# AVRI2CIO_V0_3_LEVEL0.net
KiCad netlist of a schematic drawn in EAGLE
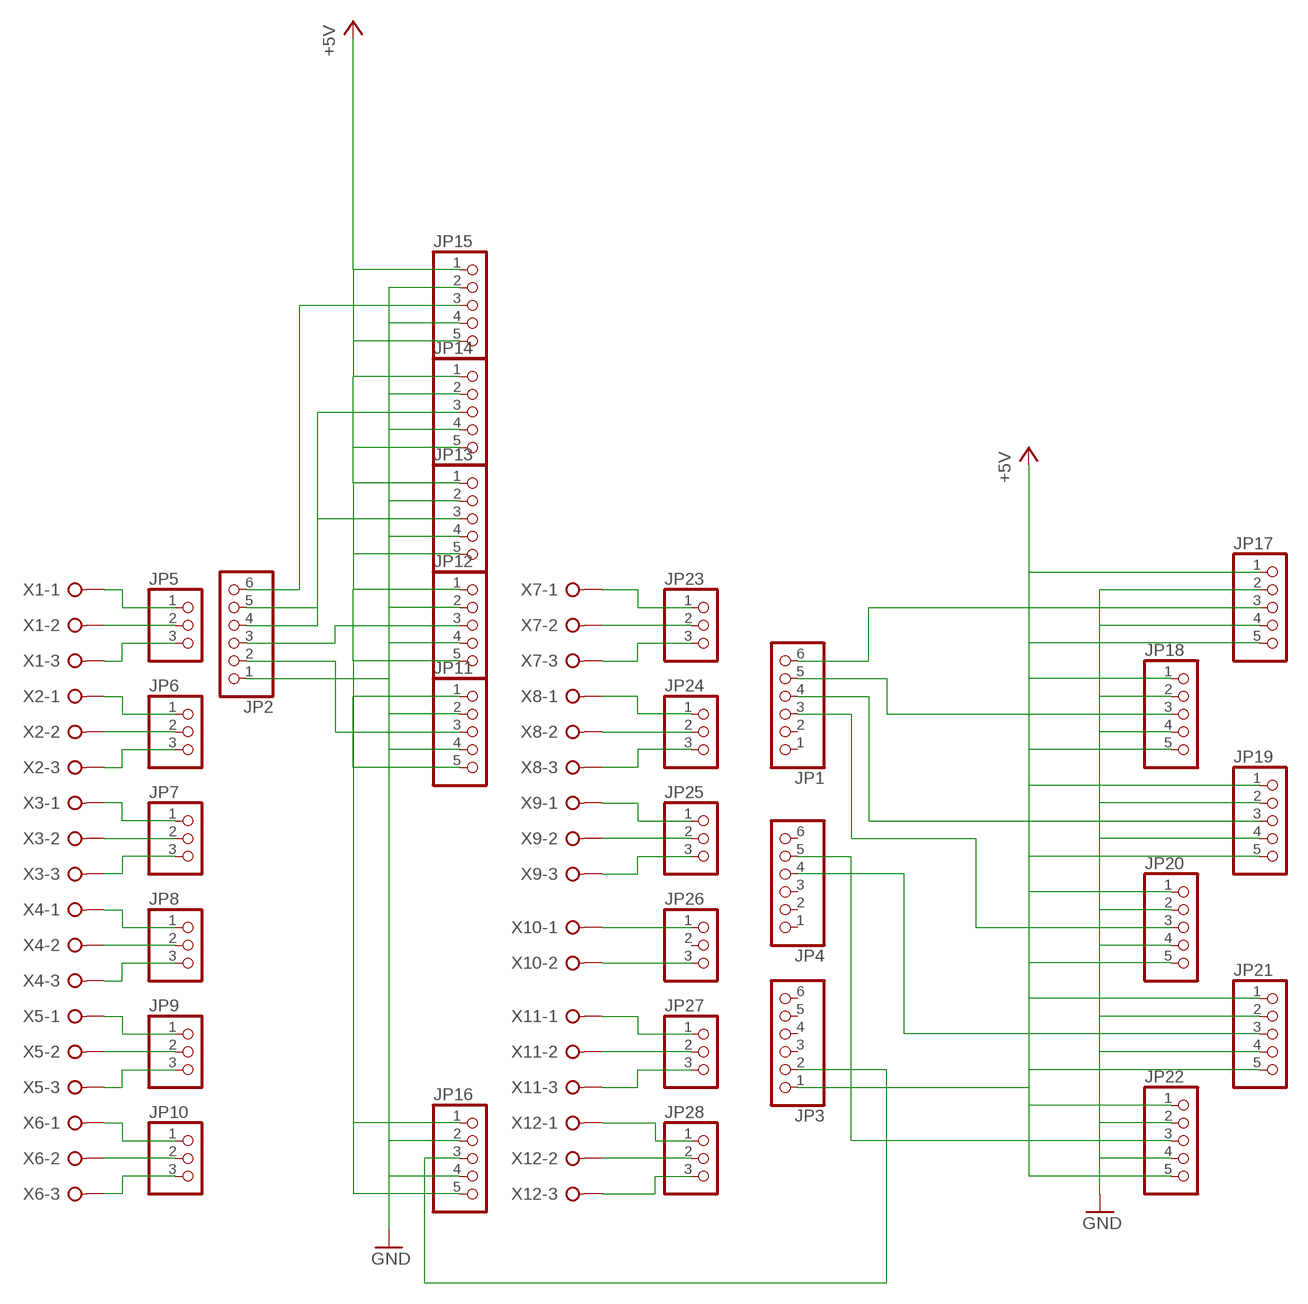
[diagram p0: schematic, sheet 1]

(export (version "E")
  (design (tool "Eeschema 10.0.6"))
  (components
    (comp (ref "JP1")
      (value "PINHD-1X6")
      (footprint "eagle-import:1X06")
      (libsource (lib "eagle-import") (part "PINHD-1X6"))
    )
    (comp (ref "JP2")
      (value "PINHD-1X6")
      (footprint "eagle-import:1X06")
      (libsource (lib "eagle-import") (part "PINHD-1X6"))
    )
    (comp (ref "JP3")
      (value "PINHD-1X6")
      (footprint "eagle-import:1X06")
      (libsource (lib "eagle-import") (part "PINHD-1X6"))
    )
    (comp (ref "JP4")
      (value "PINHD-1X6")
      (footprint "eagle-import:1X06")
      (libsource (lib "eagle-import") (part "PINHD-1X6"))
    )
    (comp (ref "JP5")
      (value "PINHD-1X3")
      (footprint "eagle-import:1X03")
      (libsource (lib "eagle-import") (part "PINHD-1X3"))
    )
    (comp (ref "JP6")
      (value "PINHD-1X3")
      (footprint "eagle-import:1X03")
      (libsource (lib "eagle-import") (part "PINHD-1X3"))
    )
    (comp (ref "JP7")
      (value "PINHD-1X3")
      (footprint "eagle-import:1X03")
      (libsource (lib "eagle-import") (part "PINHD-1X3"))
    )
    (comp (ref "JP8")
      (value "PINHD-1X3")
      (footprint "eagle-import:1X03")
      (libsource (lib "eagle-import") (part "PINHD-1X3"))
    )
    (comp (ref "JP9")
      (value "PINHD-1X3")
      (footprint "eagle-import:1X03")
      (libsource (lib "eagle-import") (part "PINHD-1X3"))
    )
    (comp (ref "JP10")
      (value "PINHD-1X3")
      (footprint "eagle-import:1X03")
      (libsource (lib "eagle-import") (part "PINHD-1X3"))
    )
    (comp (ref "JP11")
      (value "PINHD-1X5")
      (footprint "eagle-import:1X05")
      (libsource (lib "eagle-import") (part "PINHD-1X5"))
    )
    (comp (ref "JP12")
      (value "PINHD-1X5")
      (footprint "eagle-import:1X05")
      (libsource (lib "eagle-import") (part "PINHD-1X5"))
    )
    (comp (ref "JP13")
      (value "PINHD-1X5")
      (footprint "eagle-import:1X05")
      (libsource (lib "eagle-import") (part "PINHD-1X5"))
    )
    (comp (ref "JP14")
      (value "PINHD-1X5")
      (footprint "eagle-import:1X05")
      (libsource (lib "eagle-import") (part "PINHD-1X5"))
    )
    (comp (ref "JP15")
      (value "PINHD-1X5")
      (footprint "eagle-import:1X05")
      (libsource (lib "eagle-import") (part "PINHD-1X5"))
    )
    (comp (ref "JP16")
      (value "PINHD-1X5")
      (footprint "eagle-import:1X05")
      (libsource (lib "eagle-import") (part "PINHD-1X5"))
    )
    (comp (ref "JP17")
      (value "PINHD-1X5")
      (footprint "eagle-import:1X05")
      (libsource (lib "eagle-import") (part "PINHD-1X5"))
    )
    (comp (ref "JP18")
      (value "PINHD-1X5")
      (footprint "eagle-import:1X05")
      (libsource (lib "eagle-import") (part "PINHD-1X5"))
    )
    (comp (ref "JP19")
      (value "PINHD-1X5")
      (footprint "eagle-import:1X05")
      (libsource (lib "eagle-import") (part "PINHD-1X5"))
    )
    (comp (ref "JP20")
      (value "PINHD-1X5")
      (footprint "eagle-import:1X05")
      (libsource (lib "eagle-import") (part "PINHD-1X5"))
    )
    (comp (ref "JP21")
      (value "PINHD-1X5")
      (footprint "eagle-import:1X05")
      (libsource (lib "eagle-import") (part "PINHD-1X5"))
    )
    (comp (ref "JP22")
      (value "PINHD-1X5")
      (footprint "eagle-import:1X05")
      (libsource (lib "eagle-import") (part "PINHD-1X5"))
    )
    (comp (ref "JP23")
      (value "PINHD-1X3")
      (footprint "eagle-import:1X03")
      (libsource (lib "eagle-import") (part "PINHD-1X3"))
    )
    (comp (ref "JP24")
      (value "PINHD-1X3")
      (footprint "eagle-import:1X03")
      (libsource (lib "eagle-import") (part "PINHD-1X3"))
    )
    (comp (ref "JP25")
      (value "PINHD-1X3")
      (footprint "eagle-import:1X03")
      (libsource (lib "eagle-import") (part "PINHD-1X3"))
    )
    (comp (ref "JP26")
      (value "PINHD-1X3")
      (footprint "eagle-import:1X03")
      (libsource (lib "eagle-import") (part "PINHD-1X3"))
    )
    (comp (ref "JP27")
      (value "PINHD-1X3")
      (footprint "eagle-import:1X03")
      (libsource (lib "eagle-import") (part "PINHD-1X3"))
    )
    (comp (ref "JP28")
      (value "PINHD-1X3")
      (footprint "eagle-import:1X03")
      (libsource (lib "eagle-import") (part "PINHD-1X3"))
    )
    (comp (ref "X1")
      (value "W237-3E")
      (footprint "eagle-import:W237-3E")
      (libsource (lib "eagle-import") (part "W237-3E"))
    )
    (comp (ref "X2")
      (value "W237-3E")
      (footprint "eagle-import:W237-3E")
      (libsource (lib "eagle-import") (part "W237-3E"))
    )
    (comp (ref "X3")
      (value "W237-3E")
      (footprint "eagle-import:W237-3E")
      (libsource (lib "eagle-import") (part "W237-3E"))
    )
    (comp (ref "X4")
      (value "W237-3E")
      (footprint "eagle-import:W237-3E")
      (libsource (lib "eagle-import") (part "W237-3E"))
    )
    (comp (ref "X5")
      (value "W237-3E")
      (footprint "eagle-import:W237-3E")
      (libsource (lib "eagle-import") (part "W237-3E"))
    )
    (comp (ref "X6")
      (value "W237-3E")
      (footprint "eagle-import:W237-3E")
      (libsource (lib "eagle-import") (part "W237-3E"))
    )
    (comp (ref "X7")
      (value "W237-3E")
      (footprint "eagle-import:W237-3E")
      (libsource (lib "eagle-import") (part "W237-3E"))
    )
    (comp (ref "X8")
      (value "W237-3E")
      (footprint "eagle-import:W237-3E")
      (libsource (lib "eagle-import") (part "W237-3E"))
    )
    (comp (ref "X9")
      (value "W237-3E")
      (footprint "eagle-import:W237-3E")
      (libsource (lib "eagle-import") (part "W237-3E"))
    )
    (comp (ref "X10")
      (value "W237-02P")
      (footprint "eagle-import:W237-132")
      (libsource (lib "eagle-import") (part "W237-02P"))
    )
    (comp (ref "X11")
      (value "W237-3E")
      (footprint "eagle-import:W237-3E")
      (libsource (lib "eagle-import") (part "W237-3E"))
    )
    (comp (ref "X12")
      (value "W237-3E")
      (footprint "eagle-import:W237-3E")
      (libsource (lib "eagle-import") (part "W237-3E"))
    )
  )
  (nets
    (net (code "1") (name "+5V") (class "Default")
      (node (ref "JP11") (pin "1") (pinfunction "1_1") (pintype "passive"))
      (node (ref "JP11") (pin "5") (pinfunction "5_5") (pintype "passive"))
      (node (ref "JP12") (pin "1") (pinfunction "1_1") (pintype "passive"))
      (node (ref "JP12") (pin "5") (pinfunction "5_5") (pintype "passive"))
      (node (ref "JP13") (pin "1") (pinfunction "1_1") (pintype "passive"))
      (node (ref "JP13") (pin "5") (pinfunction "5_5") (pintype "passive"))
      (node (ref "JP14") (pin "1") (pinfunction "1_1") (pintype "passive"))
      (node (ref "JP14") (pin "5") (pinfunction "5_5") (pintype "passive"))
      (node (ref "JP15") (pin "1") (pinfunction "1_1") (pintype "passive"))
      (node (ref "JP15") (pin "5") (pinfunction "5_5") (pintype "passive"))
      (node (ref "JP16") (pin "1") (pinfunction "1_1") (pintype "passive"))
      (node (ref "JP16") (pin "5") (pinfunction "5_5") (pintype "passive"))
      (node (ref "JP17") (pin "1") (pinfunction "1_1") (pintype "passive"))
      (node (ref "JP17") (pin "5") (pinfunction "5_5") (pintype "passive"))
      (node (ref "JP18") (pin "1") (pinfunction "1_1") (pintype "passive"))
      (node (ref "JP18") (pin "5") (pinfunction "5_5") (pintype "passive"))
      (node (ref "JP19") (pin "1") (pinfunction "1_1") (pintype "passive"))
      (node (ref "JP19") (pin "5") (pinfunction "5_5") (pintype "passive"))
      (node (ref "JP20") (pin "1") (pinfunction "1_1") (pintype "passive"))
      (node (ref "JP20") (pin "5") (pinfunction "5_5") (pintype "passive"))
      (node (ref "JP21") (pin "1") (pinfunction "1_1") (pintype "passive"))
      (node (ref "JP21") (pin "5") (pinfunction "5_5") (pintype "passive"))
      (node (ref "JP22") (pin "1") (pinfunction "1_1") (pintype "passive"))
      (node (ref "JP22") (pin "5") (pinfunction "5_5") (pintype "passive"))
      (node (ref "JP3") (pin "1") (pinfunction "1_1") (pintype "passive"))
    )
    (net (code "2") (name "GND") (class "Default")
      (node (ref "JP11") (pin "2") (pinfunction "2_2") (pintype "passive"))
      (node (ref "JP11") (pin "4") (pinfunction "4_4") (pintype "passive"))
      (node (ref "JP12") (pin "2") (pinfunction "2_2") (pintype "passive"))
      (node (ref "JP12") (pin "4") (pinfunction "4_4") (pintype "passive"))
      (node (ref "JP13") (pin "2") (pinfunction "2_2") (pintype "passive"))
      (node (ref "JP13") (pin "4") (pinfunction "4_4") (pintype "passive"))
      (node (ref "JP14") (pin "2") (pinfunction "2_2") (pintype "passive"))
      (node (ref "JP14") (pin "4") (pinfunction "4_4") (pintype "passive"))
      (node (ref "JP15") (pin "2") (pinfunction "2_2") (pintype "passive"))
      (node (ref "JP15") (pin "4") (pinfunction "4_4") (pintype "passive"))
      (node (ref "JP16") (pin "2") (pinfunction "2_2") (pintype "passive"))
      (node (ref "JP16") (pin "4") (pinfunction "4_4") (pintype "passive"))
      (node (ref "JP17") (pin "2") (pinfunction "2_2") (pintype "passive"))
      (node (ref "JP17") (pin "4") (pinfunction "4_4") (pintype "passive"))
      (node (ref "JP18") (pin "2") (pinfunction "2_2") (pintype "passive"))
      (node (ref "JP18") (pin "4") (pinfunction "4_4") (pintype "passive"))
      (node (ref "JP19") (pin "2") (pinfunction "2_2") (pintype "passive"))
      (node (ref "JP19") (pin "4") (pinfunction "4_4") (pintype "passive"))
      (node (ref "JP2") (pin "1") (pinfunction "1_1") (pintype "passive"))
      (node (ref "JP20") (pin "2") (pinfunction "2_2") (pintype "passive"))
      (node (ref "JP20") (pin "4") (pinfunction "4_4") (pintype "passive"))
      (node (ref "JP21") (pin "2") (pinfunction "2_2") (pintype "passive"))
      (node (ref "JP21") (pin "4") (pinfunction "4_4") (pintype "passive"))
      (node (ref "JP22") (pin "2") (pinfunction "2_2") (pintype "passive"))
      (node (ref "JP22") (pin "4") (pinfunction "4_4") (pintype "passive"))
    )
    (net (code "3") (name "Net-(JP1-Pad3)") (class "Default")
      (node (ref "JP1") (pin "3") (pinfunction "3_3") (pintype "passive"))
      (node (ref "JP20") (pin "3") (pinfunction "3_3") (pintype "passive"))
    )
    (net (code "4") (name "Net-(JP1-Pad4)") (class "Default")
      (node (ref "JP1") (pin "4") (pinfunction "4_4") (pintype "passive"))
      (node (ref "JP19") (pin "3") (pinfunction "3_3") (pintype "passive"))
    )
    (net (code "5") (name "Net-(JP1-Pad5)") (class "Default")
      (node (ref "JP1") (pin "5") (pinfunction "5_5") (pintype "passive"))
      (node (ref "JP18") (pin "3") (pinfunction "3_3") (pintype "passive"))
    )
    (net (code "6") (name "Net-(JP1-Pad6)") (class "Default")
      (node (ref "JP1") (pin "6") (pinfunction "6_6") (pintype "passive"))
      (node (ref "JP17") (pin "3") (pinfunction "3_3") (pintype "passive"))
    )
    (net (code "7") (name "Net-(JP11-Pad3)") (class "Default")
      (node (ref "JP11") (pin "3") (pinfunction "3_3") (pintype "passive"))
      (node (ref "JP2") (pin "2") (pinfunction "2_2") (pintype "passive"))
    )
    (net (code "8") (name "Net-(JP12-Pad3)") (class "Default")
      (node (ref "JP12") (pin "3") (pinfunction "3_3") (pintype "passive"))
      (node (ref "JP2") (pin "3") (pinfunction "3_3") (pintype "passive"))
    )
    (net (code "9") (name "Net-(JP13-Pad3)") (class "Default")
      (node (ref "JP13") (pin "3") (pinfunction "3_3") (pintype "passive"))
      (node (ref "JP2") (pin "4") (pinfunction "4_4") (pintype "passive"))
    )
    (net (code "10") (name "Net-(JP14-Pad3)") (class "Default")
      (node (ref "JP14") (pin "3") (pinfunction "3_3") (pintype "passive"))
      (node (ref "JP2") (pin "5") (pinfunction "5_5") (pintype "passive"))
    )
    (net (code "11") (name "Net-(JP15-Pad3)") (class "Default")
      (node (ref "JP15") (pin "3") (pinfunction "3_3") (pintype "passive"))
      (node (ref "JP2") (pin "6") (pinfunction "6_6") (pintype "passive"))
    )
    (net (code "12") (name "Net-(JP16-Pad3)") (class "Default")
      (node (ref "JP16") (pin "3") (pinfunction "3_3") (pintype "passive"))
      (node (ref "JP3") (pin "2") (pinfunction "2_2") (pintype "passive"))
    )
    (net (code "13") (name "Net-(JP21-Pad3)") (class "Default")
      (node (ref "JP21") (pin "3") (pinfunction "3_3") (pintype "passive"))
      (node (ref "JP4") (pin "4") (pinfunction "4_4") (pintype "passive"))
    )
    (net (code "14") (name "Net-(JP22-Pad3)") (class "Default")
      (node (ref "JP22") (pin "3") (pinfunction "3_3") (pintype "passive"))
      (node (ref "JP4") (pin "5") (pinfunction "5_5") (pintype "passive"))
    )
    (net (code "15") (name "Net-(X1A-KL)") (class "Default")
      (node (ref "JP5") (pin "1") (pinfunction "1_1") (pintype "passive"))
      (node (ref "X1") (pin "1") (pinfunction "KL_1") (pintype "passive"))
    )
    (net (code "16") (name "Net-(X1B-KL)") (class "Default")
      (node (ref "JP5") (pin "2") (pinfunction "2_2") (pintype "passive"))
      (node (ref "X1") (pin "2") (pinfunction "KL_2") (pintype "passive"))
    )
    (net (code "17") (name "Net-(X1C-KL)") (class "Default")
      (node (ref "JP5") (pin "3") (pinfunction "3_3") (pintype "passive"))
      (node (ref "X1") (pin "3") (pinfunction "KL_3") (pintype "passive"))
    )
    (net (code "18") (name "Net-(X2A-KL)") (class "Default")
      (node (ref "JP6") (pin "1") (pinfunction "1_1") (pintype "passive"))
      (node (ref "X2") (pin "1") (pinfunction "KL_1") (pintype "passive"))
    )
    (net (code "19") (name "Net-(X2B-KL)") (class "Default")
      (node (ref "JP6") (pin "2") (pinfunction "2_2") (pintype "passive"))
      (node (ref "X2") (pin "2") (pinfunction "KL_2") (pintype "passive"))
    )
    (net (code "20") (name "Net-(X2C-KL)") (class "Default")
      (node (ref "JP6") (pin "3") (pinfunction "3_3") (pintype "passive"))
      (node (ref "X2") (pin "3") (pinfunction "KL_3") (pintype "passive"))
    )
    (net (code "21") (name "Net-(X3A-KL)") (class "Default")
      (node (ref "JP7") (pin "1") (pinfunction "1_1") (pintype "passive"))
      (node (ref "X3") (pin "1") (pinfunction "KL_1") (pintype "passive"))
    )
    (net (code "22") (name "Net-(X3B-KL)") (class "Default")
      (node (ref "JP7") (pin "2") (pinfunction "2_2") (pintype "passive"))
      (node (ref "X3") (pin "2") (pinfunction "KL_2") (pintype "passive"))
    )
    (net (code "23") (name "Net-(X3C-KL)") (class "Default")
      (node (ref "JP7") (pin "3") (pinfunction "3_3") (pintype "passive"))
      (node (ref "X3") (pin "3") (pinfunction "KL_3") (pintype "passive"))
    )
    (net (code "24") (name "Net-(X4A-KL)") (class "Default")
      (node (ref "JP8") (pin "1") (pinfunction "1_1") (pintype "passive"))
      (node (ref "X4") (pin "1") (pinfunction "KL_1") (pintype "passive"))
    )
    (net (code "25") (name "Net-(X4B-KL)") (class "Default")
      (node (ref "JP8") (pin "2") (pinfunction "2_2") (pintype "passive"))
      (node (ref "X4") (pin "2") (pinfunction "KL_2") (pintype "passive"))
    )
    (net (code "26") (name "Net-(X4C-KL)") (class "Default")
      (node (ref "JP8") (pin "3") (pinfunction "3_3") (pintype "passive"))
      (node (ref "X4") (pin "3") (pinfunction "KL_3") (pintype "passive"))
    )
    (net (code "27") (name "Net-(X5A-KL)") (class "Default")
      (node (ref "JP9") (pin "1") (pinfunction "1_1") (pintype "passive"))
      (node (ref "X5") (pin "1") (pinfunction "KL_1") (pintype "passive"))
    )
    (net (code "28") (name "Net-(X5B-KL)") (class "Default")
      (node (ref "JP9") (pin "2") (pinfunction "2_2") (pintype "passive"))
      (node (ref "X5") (pin "2") (pinfunction "KL_2") (pintype "passive"))
    )
    (net (code "29") (name "Net-(X5C-KL)") (class "Default")
      (node (ref "JP9") (pin "3") (pinfunction "3_3") (pintype "passive"))
      (node (ref "X5") (pin "3") (pinfunction "KL_3") (pintype "passive"))
    )
    (net (code "30") (name "Net-(X6A-KL)") (class "Default")
      (node (ref "JP10") (pin "1") (pinfunction "1_1") (pintype "passive"))
      (node (ref "X6") (pin "1") (pinfunction "KL_1") (pintype "passive"))
    )
    (net (code "31") (name "Net-(X6B-KL)") (class "Default")
      (node (ref "JP10") (pin "2") (pinfunction "2_2") (pintype "passive"))
      (node (ref "X6") (pin "2") (pinfunction "KL_2") (pintype "passive"))
    )
    (net (code "32") (name "Net-(X6C-KL)") (class "Default")
      (node (ref "JP10") (pin "3") (pinfunction "3_3") (pintype "passive"))
      (node (ref "X6") (pin "3") (pinfunction "KL_3") (pintype "passive"))
    )
    (net (code "33") (name "Net-(X7A-KL)") (class "Default")
      (node (ref "JP23") (pin "1") (pinfunction "1_1") (pintype "passive"))
      (node (ref "X7") (pin "1") (pinfunction "KL_1") (pintype "passive"))
    )
    (net (code "34") (name "Net-(X7B-KL)") (class "Default")
      (node (ref "JP23") (pin "2") (pinfunction "2_2") (pintype "passive"))
      (node (ref "X7") (pin "2") (pinfunction "KL_2") (pintype "passive"))
    )
    (net (code "35") (name "Net-(X7C-KL)") (class "Default")
      (node (ref "JP23") (pin "3") (pinfunction "3_3") (pintype "passive"))
      (node (ref "X7") (pin "3") (pinfunction "KL_3") (pintype "passive"))
    )
    (net (code "36") (name "Net-(X8A-KL)") (class "Default")
      (node (ref "JP24") (pin "1") (pinfunction "1_1") (pintype "passive"))
      (node (ref "X8") (pin "1") (pinfunction "KL_1") (pintype "passive"))
    )
    (net (code "37") (name "Net-(X8B-KL)") (class "Default")
      (node (ref "JP24") (pin "2") (pinfunction "2_2") (pintype "passive"))
      (node (ref "X8") (pin "2") (pinfunction "KL_2") (pintype "passive"))
    )
    (net (code "38") (name "Net-(X8C-KL)") (class "Default")
      (node (ref "JP24") (pin "3") (pinfunction "3_3") (pintype "passive"))
      (node (ref "X8") (pin "3") (pinfunction "KL_3") (pintype "passive"))
    )
    (net (code "39") (name "Net-(X9A-KL)") (class "Default")
      (node (ref "JP25") (pin "1") (pinfunction "1_1") (pintype "passive"))
      (node (ref "X9") (pin "1") (pinfunction "KL_1") (pintype "passive"))
    )
    (net (code "40") (name "Net-(X9B-KL)") (class "Default")
      (node (ref "JP25") (pin "2") (pinfunction "2_2") (pintype "passive"))
      (node (ref "X9") (pin "2") (pinfunction "KL_2") (pintype "passive"))
    )
    (net (code "41") (name "Net-(X9C-KL)") (class "Default")
      (node (ref "JP25") (pin "3") (pinfunction "3_3") (pintype "passive"))
      (node (ref "X9") (pin "3") (pinfunction "KL_3") (pintype "passive"))
    )
    (net (code "42") (name "Net-(X10A-KL)") (class "Default")
      (node (ref "JP26") (pin "1") (pinfunction "1_1") (pintype "passive"))
      (node (ref "X10") (pin "1") (pinfunction "KL_1") (pintype "passive"))
    )
    (net (code "43") (name "Net-(X10B-KL)") (class "Default")
      (node (ref "JP26") (pin "3") (pinfunction "3_3") (pintype "passive"))
      (node (ref "X10") (pin "2") (pinfunction "KL_2") (pintype "passive"))
    )
    (net (code "44") (name "Net-(X11A-KL)") (class "Default")
      (node (ref "JP27") (pin "1") (pinfunction "1_1") (pintype "passive"))
      (node (ref "X11") (pin "1") (pinfunction "KL_1") (pintype "passive"))
    )
    (net (code "45") (name "Net-(X11B-KL)") (class "Default")
      (node (ref "JP27") (pin "2") (pinfunction "2_2") (pintype "passive"))
      (node (ref "X11") (pin "2") (pinfunction "KL_2") (pintype "passive"))
    )
    (net (code "46") (name "Net-(X11C-KL)") (class "Default")
      (node (ref "JP27") (pin "3") (pinfunction "3_3") (pintype "passive"))
      (node (ref "X11") (pin "3") (pinfunction "KL_3") (pintype "passive"))
    )
    (net (code "47") (name "Net-(X12A-KL)") (class "Default")
      (node (ref "JP28") (pin "1") (pinfunction "1_1") (pintype "passive"))
      (node (ref "X12") (pin "1") (pinfunction "KL_1") (pintype "passive"))
    )
    (net (code "48") (name "Net-(X12B-KL)") (class "Default")
      (node (ref "JP28") (pin "2") (pinfunction "2_2") (pintype "passive"))
      (node (ref "X12") (pin "2") (pinfunction "KL_2") (pintype "passive"))
    )
    (net (code "49") (name "Net-(X12C-KL)") (class "Default")
      (node (ref "JP28") (pin "3") (pinfunction "3_3") (pintype "passive"))
      (node (ref "X12") (pin "3") (pinfunction "KL_3") (pintype "passive"))
    )
    (net (code "50") (name "unconnected-(JP1-Pad1)") (class "Default")
      (node (ref "JP1") (pin "1") (pinfunction "1_1") (pintype "passive"))
    )
    (net (code "51") (name "unconnected-(JP1-Pad2)") (class "Default")
      (node (ref "JP1") (pin "2") (pinfunction "2_2") (pintype "passive"))
    )
    (net (code "52") (name "unconnected-(JP3-Pad3)") (class "Default")
      (node (ref "JP3") (pin "3") (pinfunction "3_3") (pintype "passive"))
    )
    (net (code "53") (name "unconnected-(JP3-Pad4)") (class "Default")
      (node (ref "JP3") (pin "4") (pinfunction "4_4") (pintype "passive"))
    )
    (net (code "54") (name "unconnected-(JP3-Pad5)") (class "Default")
      (node (ref "JP3") (pin "5") (pinfunction "5_5") (pintype "passive"))
    )
    (net (code "55") (name "unconnected-(JP3-Pad6)") (class "Default")
      (node (ref "JP3") (pin "6") (pinfunction "6_6") (pintype "passive"))
    )
    (net (code "56") (name "unconnected-(JP4-Pad1)") (class "Default")
      (node (ref "JP4") (pin "1") (pinfunction "1_1") (pintype "passive"))
    )
    (net (code "57") (name "unconnected-(JP4-Pad2)") (class "Default")
      (node (ref "JP4") (pin "2") (pinfunction "2_2") (pintype "passive"))
    )
    (net (code "58") (name "unconnected-(JP4-Pad3)") (class "Default")
      (node (ref "JP4") (pin "3") (pinfunction "3_3") (pintype "passive"))
    )
    (net (code "59") (name "unconnected-(JP4-Pad6)") (class "Default")
      (node (ref "JP4") (pin "6") (pinfunction "6_6") (pintype "passive"))
    )
    (net (code "60") (name "unconnected-(JP26-Pad2)") (class "Default")
      (node (ref "JP26") (pin "2") (pinfunction "2_2") (pintype "passive"))
    )
  )
)
